# shield.net
KiCad netlist of a schematic drawn in EAGLE
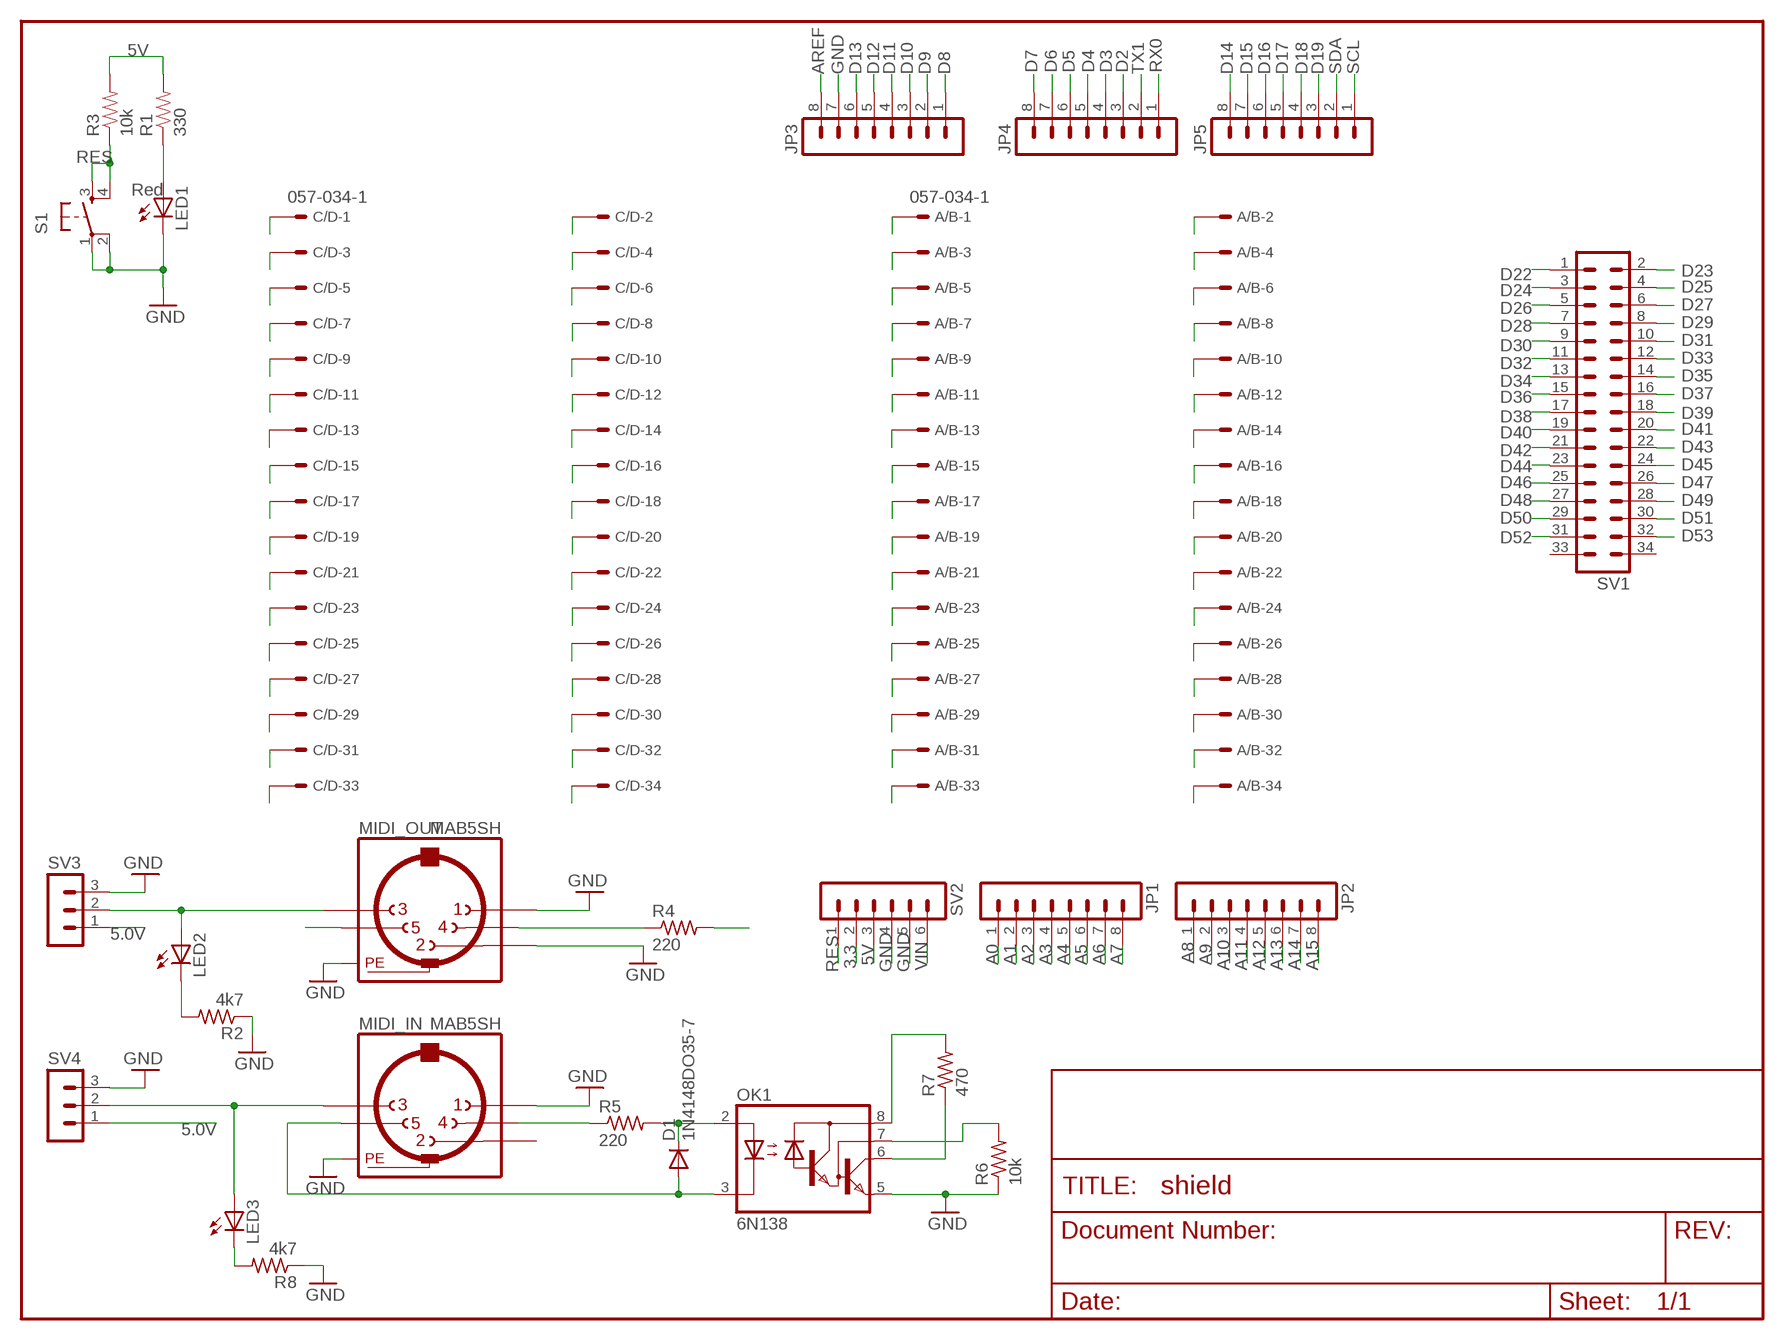
[diagram p0: schematic, sheet 1]

(export (version "E")
  (design (tool "Eeschema 10.0.6"))
  (components
    (comp (ref "A/B")
      (value "057-034-1")
      (footprint "eagle-import:057-034-1")
      (libsource (lib "eagle-import") (part "057-034-1"))
    )
    (comp (ref "C/D")
      (value "057-034-1")
      (footprint "eagle-import:057-034-1")
      (libsource (lib "eagle-import") (part "057-034-1"))
    )
    (comp (ref "D1")
      (value "1N4148DO35-7")
      (footprint "eagle-import:DO35-7")
      (libsource (lib "eagle-import") (part "1N4148DO35-7"))
    )
    (comp (ref "JP1")
      (value "MA08-1")
      (footprint "eagle-import:MA08-1")
      (libsource (lib "eagle-import") (part "MA08-1"))
    )
    (comp (ref "JP2")
      (value "MA08-1")
      (footprint "eagle-import:MA08-1")
      (libsource (lib "eagle-import") (part "MA08-1"))
    )
    (comp (ref "JP3")
      (value "MA08-1")
      (footprint "eagle-import:MA08-1")
      (libsource (lib "eagle-import") (part "MA08-1"))
    )
    (comp (ref "JP4")
      (value "MA08-1")
      (footprint "eagle-import:MA08-1")
      (libsource (lib "eagle-import") (part "MA08-1"))
    )
    (comp (ref "JP5")
      (value "MA08-1")
      (footprint "eagle-import:MA08-1")
      (libsource (lib "eagle-import") (part "MA08-1"))
    )
    (comp (ref "LED1")
      (value "Red")
      (footprint "eagle-import:LED5MM")
      (libsource (lib "eagle-import") (part "LED5MM"))
    )
    (comp (ref "LED2")
      (value "LEDLSU260")
      (footprint "eagle-import:LSU260")
      (libsource (lib "eagle-import") (part "LEDLSU260"))
    )
    (comp (ref "LED3")
      (value "LEDLSU260")
      (footprint "eagle-import:LSU260")
      (libsource (lib "eagle-import") (part "LEDLSU260"))
    )
    (comp (ref "MIDI_IN")
      (value "MAB5SH")
      (footprint "eagle-import:MAB5SH")
      (libsource (lib "eagle-import") (part "MAB5SH"))
    )
    (comp (ref "MIDI_OUT")
      (value "MAB5SH")
      (footprint "eagle-import:MAB5SH")
      (libsource (lib "eagle-import") (part "MAB5SH"))
    )
    (comp (ref "OK1")
      (value "6N138")
      (footprint "eagle-import:DIL08")
      (fields (field (name "MF") "VISHAY/TELEFUNKEN"))
      (libsource (lib "eagle-import") (part "6N138"))
    )
    (comp (ref "R1")
      (value "330")
      (footprint "eagle-import:AXIAL-0.3")
      (libsource (lib "eagle-import") (part "RESISTORPTH1"))
    )
    (comp (ref "R2")
      (value "4k7")
      (footprint "eagle-import:0204_7")
      (libsource (lib "eagle-import") (part "resistor_R-US_0204/7"))
    )
    (comp (ref "R3")
      (value "10k")
      (footprint "eagle-import:AXIAL-0.3")
      (libsource (lib "eagle-import") (part "RESISTORPTH1"))
    )
    (comp (ref "R4")
      (value "220")
      (footprint "eagle-import:0204_7")
      (libsource (lib "eagle-import") (part "R-US_0204/7"))
    )
    (comp (ref "R5")
      (value "220")
      (footprint "eagle-import:0204_7")
      (libsource (lib "eagle-import") (part "R-US_0204/7"))
    )
    (comp (ref "R6")
      (value "10k")
      (footprint "eagle-import:0204_7")
      (libsource (lib "eagle-import") (part "R-US_0204/7"))
    )
    (comp (ref "R7")
      (value "470")
      (footprint "eagle-import:0204_7")
      (libsource (lib "eagle-import") (part "R-US_0204/7"))
    )
    (comp (ref "R8")
      (value "4k7")
      (footprint "eagle-import:0204_7")
      (libsource (lib "eagle-import") (part "resistor_R-US_0204/7"))
    )
    (comp (ref "S1")
      (value "TAC_SWITCHPTH")
      (footprint "eagle-import:TACTILE-PTH")
      (libsource (lib "eagle-import") (part "TAC_SWITCHPTH"))
    )
    (comp (ref "SV1")
      (value "MA17-2")
      (footprint "eagle-import:MA17-2")
      (libsource (lib "eagle-import") (part "MA17-2"))
    )
    (comp (ref "SV2")
      (value "MA06-1")
      (footprint "eagle-import:MA06-1")
      (libsource (lib "eagle-import") (part "MA06-1"))
    )
    (comp (ref "SV3")
      (value "MA03-1")
      (footprint "eagle-import:MA03-1")
      (libsource (lib "eagle-import") (part "MA03-1"))
    )
    (comp (ref "SV4")
      (value "MA03-1")
      (footprint "eagle-import:MA03-1")
      (libsource (lib "eagle-import") (part "MA03-1"))
    )
  )
  (nets
    (net (code "1") (name "/3.3") (class "Default")
      (node (ref "SV2") (pin "2") (pinfunction "2_2") (pintype "passive"))
    )
    (net (code "2") (name "/5.0V") (class "Default")
      (node (ref "A/B") (pin "33") (pinfunction "S_33") (pintype "passive"))
      (node (ref "C/D") (pin "2") (pinfunction "S_2") (pintype "passive"))
      (node (ref "C/D") (pin "33") (pinfunction "S_33") (pintype "passive"))
      (node (ref "OK1") (pin "8") (pinfunction "VCC_8") (pintype "passive"))
      (node (ref "R1") (pin "P$2") (pinfunction "2_P$2") (pintype "passive"))
      (node (ref "R3") (pin "P$2") (pinfunction "2_P$2") (pintype "passive"))
      (node (ref "R4") (pin "2") (pinfunction "2_2") (pintype "passive"))
      (node (ref "R7") (pin "2") (pinfunction "2_2") (pintype "passive"))
      (node (ref "SV2") (pin "3") (pinfunction "3_3") (pintype "passive"))
      (node (ref "SV3") (pin "1") (pinfunction "1_1") (pintype "passive"))
      (node (ref "SV4") (pin "1") (pinfunction "1_1") (pintype "passive"))
    )
    (net (code "3") (name "/A0") (class "Default")
      (node (ref "JP1") (pin "1") (pinfunction "1_1") (pintype "passive"))
    )
    (net (code "4") (name "/A1") (class "Default")
      (node (ref "JP1") (pin "2") (pinfunction "2_2") (pintype "passive"))
    )
    (net (code "5") (name "/A2") (class "Default")
      (node (ref "JP1") (pin "3") (pinfunction "3_3") (pintype "passive"))
    )
    (net (code "6") (name "/A3") (class "Default")
      (node (ref "JP1") (pin "4") (pinfunction "4_4") (pintype "passive"))
    )
    (net (code "7") (name "/A4") (class "Default")
      (node (ref "C/D") (pin "9") (pinfunction "S_9") (pintype "passive"))
      (node (ref "JP1") (pin "5") (pinfunction "5_5") (pintype "passive"))
    )
    (net (code "8") (name "/A5") (class "Default")
      (node (ref "C/D") (pin "11") (pinfunction "S_11") (pintype "passive"))
      (node (ref "JP1") (pin "6") (pinfunction "6_6") (pintype "passive"))
    )
    (net (code "9") (name "/A6") (class "Default")
      (node (ref "C/D") (pin "13") (pinfunction "S_13") (pintype "passive"))
      (node (ref "JP1") (pin "7") (pinfunction "7_7") (pintype "passive"))
    )
    (net (code "10") (name "/A7") (class "Default")
      (node (ref "C/D") (pin "15") (pinfunction "S_15") (pintype "passive"))
      (node (ref "JP1") (pin "8") (pinfunction "8_8") (pintype "passive"))
    )
    (net (code "11") (name "/A8") (class "Default")
      (node (ref "C/D") (pin "17") (pinfunction "S_17") (pintype "passive"))
      (node (ref "JP2") (pin "1") (pinfunction "1_1") (pintype "passive"))
    )
    (net (code "12") (name "/A9") (class "Default")
      (node (ref "C/D") (pin "19") (pinfunction "S_19") (pintype "passive"))
      (node (ref "JP2") (pin "2") (pinfunction "2_2") (pintype "passive"))
    )
    (net (code "13") (name "/A10") (class "Default")
      (node (ref "C/D") (pin "21") (pinfunction "S_21") (pintype "passive"))
      (node (ref "JP2") (pin "3") (pinfunction "3_3") (pintype "passive"))
    )
    (net (code "14") (name "/A11") (class "Default")
      (node (ref "C/D") (pin "23") (pinfunction "S_23") (pintype "passive"))
      (node (ref "JP2") (pin "4") (pinfunction "4_4") (pintype "passive"))
    )
    (net (code "15") (name "/A12") (class "Default")
      (node (ref "C/D") (pin "25") (pinfunction "S_25") (pintype "passive"))
      (node (ref "JP2") (pin "5") (pinfunction "5_5") (pintype "passive"))
    )
    (net (code "16") (name "/A13") (class "Default")
      (node (ref "C/D") (pin "27") (pinfunction "S_27") (pintype "passive"))
      (node (ref "JP2") (pin "6") (pinfunction "6_6") (pintype "passive"))
    )
    (net (code "17") (name "/A14") (class "Default")
      (node (ref "C/D") (pin "29") (pinfunction "S_29") (pintype "passive"))
      (node (ref "JP2") (pin "7") (pinfunction "7_7") (pintype "passive"))
    )
    (net (code "18") (name "/A15") (class "Default")
      (node (ref "C/D") (pin "31") (pinfunction "S_31") (pintype "passive"))
      (node (ref "JP2") (pin "8") (pinfunction "8_8") (pintype "passive"))
    )
    (net (code "19") (name "/AREF") (class "Default")
      (node (ref "JP3") (pin "8") (pinfunction "8_8") (pintype "passive"))
    )
    (net (code "20") (name "/D2") (class "Default")
      (node (ref "A/B") (pin "26") (pinfunction "S_26") (pintype "passive"))
      (node (ref "JP4") (pin "3") (pinfunction "3_3") (pintype "passive"))
    )
    (net (code "21") (name "/D3") (class "Default")
      (node (ref "A/B") (pin "24") (pinfunction "S_24") (pintype "passive"))
      (node (ref "JP4") (pin "4") (pinfunction "4_4") (pintype "passive"))
    )
    (net (code "22") (name "/D4") (class "Default")
      (node (ref "A/B") (pin "22") (pinfunction "S_22") (pintype "passive"))
      (node (ref "JP4") (pin "5") (pinfunction "5_5") (pintype "passive"))
    )
    (net (code "23") (name "/D5") (class "Default")
      (node (ref "A/B") (pin "20") (pinfunction "S_20") (pintype "passive"))
      (node (ref "JP4") (pin "6") (pinfunction "6_6") (pintype "passive"))
    )
    (net (code "24") (name "/D6") (class "Default")
      (node (ref "A/B") (pin "18") (pinfunction "S_18") (pintype "passive"))
      (node (ref "JP4") (pin "7") (pinfunction "7_7") (pintype "passive"))
    )
    (net (code "25") (name "/D7") (class "Default")
      (node (ref "A/B") (pin "16") (pinfunction "S_16") (pintype "passive"))
      (node (ref "JP4") (pin "8") (pinfunction "8_8") (pintype "passive"))
    )
    (net (code "26") (name "/D8") (class "Default")
      (node (ref "A/B") (pin "14") (pinfunction "S_14") (pintype "passive"))
      (node (ref "JP3") (pin "1") (pinfunction "1_1") (pintype "passive"))
    )
    (net (code "27") (name "/D9") (class "Default")
      (node (ref "A/B") (pin "12") (pinfunction "S_12") (pintype "passive"))
      (node (ref "JP3") (pin "2") (pinfunction "2_2") (pintype "passive"))
    )
    (net (code "28") (name "/D10") (class "Default")
      (node (ref "A/B") (pin "10") (pinfunction "S_10") (pintype "passive"))
      (node (ref "JP3") (pin "3") (pinfunction "3_3") (pintype "passive"))
    )
    (net (code "29") (name "/D11") (class "Default")
      (node (ref "A/B") (pin "8") (pinfunction "S_8") (pintype "passive"))
      (node (ref "JP3") (pin "4") (pinfunction "4_4") (pintype "passive"))
    )
    (net (code "30") (name "/D12") (class "Default")
      (node (ref "A/B") (pin "6") (pinfunction "S_6") (pintype "passive"))
      (node (ref "JP3") (pin "5") (pinfunction "5_5") (pintype "passive"))
    )
    (net (code "31") (name "/D13") (class "Default")
      (node (ref "A/B") (pin "4") (pinfunction "S_4") (pintype "passive"))
      (node (ref "JP3") (pin "6") (pinfunction "6_6") (pintype "passive"))
    )
    (net (code "32") (name "/D14") (class "Default")
      (node (ref "JP5") (pin "8") (pinfunction "8_8") (pintype "passive"))
    )
    (net (code "33") (name "/D15") (class "Default")
      (node (ref "JP5") (pin "7") (pinfunction "7_7") (pintype "passive"))
    )
    (net (code "34") (name "/D16") (class "Default")
      (node (ref "JP5") (pin "6") (pinfunction "6_6") (pintype "passive"))
    )
    (net (code "35") (name "/D17") (class "Default")
      (node (ref "JP5") (pin "5") (pinfunction "5_5") (pintype "passive"))
    )
    (net (code "36") (name "/D18") (class "Default")
      (node (ref "JP5") (pin "4") (pinfunction "4_4") (pintype "passive"))
      (node (ref "MIDI_OUT") (pin "5") (pinfunction "5_5") (pintype "passive"))
    )
    (net (code "37") (name "/D19") (class "Default")
      (node (ref "JP5") (pin "3") (pinfunction "3_3") (pintype "passive"))
      (node (ref "OK1") (pin "6") (pinfunction "VO_6") (pintype "passive"))
      (node (ref "R7") (pin "1") (pinfunction "1_1") (pintype "passive"))
    )
    (net (code "38") (name "/D22") (class "Default")
      (node (ref "A/B") (pin "9") (pinfunction "S_9") (pintype "passive"))
      (node (ref "SV1") (pin "1") (pinfunction "1_1") (pintype "passive"))
    )
    (net (code "39") (name "/D23") (class "Default")
      (node (ref "A/B") (pin "11") (pinfunction "S_11") (pintype "passive"))
      (node (ref "SV1") (pin "2") (pinfunction "2_2") (pintype "passive"))
    )
    (net (code "40") (name "/D24") (class "Default")
      (node (ref "A/B") (pin "13") (pinfunction "S_13") (pintype "passive"))
      (node (ref "SV1") (pin "3") (pinfunction "3_3") (pintype "passive"))
    )
    (net (code "41") (name "/D25") (class "Default")
      (node (ref "A/B") (pin "15") (pinfunction "S_15") (pintype "passive"))
      (node (ref "SV1") (pin "4") (pinfunction "4_4") (pintype "passive"))
    )
    (net (code "42") (name "/D26") (class "Default")
      (node (ref "A/B") (pin "17") (pinfunction "S_17") (pintype "passive"))
      (node (ref "SV1") (pin "5") (pinfunction "5_5") (pintype "passive"))
    )
    (net (code "43") (name "/D27") (class "Default")
      (node (ref "A/B") (pin "19") (pinfunction "S_19") (pintype "passive"))
      (node (ref "SV1") (pin "6") (pinfunction "6_6") (pintype "passive"))
    )
    (net (code "44") (name "/D28") (class "Default")
      (node (ref "A/B") (pin "21") (pinfunction "S_21") (pintype "passive"))
      (node (ref "SV1") (pin "7") (pinfunction "7_7") (pintype "passive"))
    )
    (net (code "45") (name "/D29") (class "Default")
      (node (ref "A/B") (pin "31") (pinfunction "S_31") (pintype "passive"))
      (node (ref "SV1") (pin "8") (pinfunction "8_8") (pintype "passive"))
    )
    (net (code "46") (name "/D30") (class "Default")
      (node (ref "A/B") (pin "29") (pinfunction "S_29") (pintype "passive"))
      (node (ref "SV1") (pin "9") (pinfunction "9_9") (pintype "passive"))
    )
    (net (code "47") (name "/D31") (class "Default")
      (node (ref "A/B") (pin "27") (pinfunction "S_27") (pintype "passive"))
      (node (ref "SV1") (pin "10") (pinfunction "10_10") (pintype "passive"))
    )
    (net (code "48") (name "/D32") (class "Default")
      (node (ref "A/B") (pin "25") (pinfunction "S_25") (pintype "passive"))
      (node (ref "SV1") (pin "11") (pinfunction "11_11") (pintype "passive"))
    )
    (net (code "49") (name "/D33") (class "Default")
      (node (ref "A/B") (pin "23") (pinfunction "S_23") (pintype "passive"))
      (node (ref "SV1") (pin "12") (pinfunction "12_12") (pintype "passive"))
    )
    (net (code "50") (name "/D34") (class "Default")
      (node (ref "C/D") (pin "4") (pinfunction "S_4") (pintype "passive"))
      (node (ref "SV1") (pin "13") (pinfunction "13_13") (pintype "passive"))
    )
    (net (code "51") (name "/D35") (class "Default")
      (node (ref "C/D") (pin "6") (pinfunction "S_6") (pintype "passive"))
      (node (ref "SV1") (pin "14") (pinfunction "14_14") (pintype "passive"))
    )
    (net (code "52") (name "/D36") (class "Default")
      (node (ref "C/D") (pin "8") (pinfunction "S_8") (pintype "passive"))
      (node (ref "SV1") (pin "15") (pinfunction "15_15") (pintype "passive"))
    )
    (net (code "53") (name "/D37") (class "Default")
      (node (ref "C/D") (pin "10") (pinfunction "S_10") (pintype "passive"))
      (node (ref "SV1") (pin "16") (pinfunction "16_16") (pintype "passive"))
    )
    (net (code "54") (name "/D38") (class "Default")
      (node (ref "C/D") (pin "12") (pinfunction "S_12") (pintype "passive"))
      (node (ref "SV1") (pin "17") (pinfunction "17_17") (pintype "passive"))
    )
    (net (code "55") (name "/D39") (class "Default")
      (node (ref "C/D") (pin "14") (pinfunction "S_14") (pintype "passive"))
      (node (ref "SV1") (pin "18") (pinfunction "18_18") (pintype "passive"))
    )
    (net (code "56") (name "/D40") (class "Default")
      (node (ref "C/D") (pin "16") (pinfunction "S_16") (pintype "passive"))
      (node (ref "SV1") (pin "19") (pinfunction "19_19") (pintype "passive"))
    )
    (net (code "57") (name "/D41") (class "Default")
      (node (ref "C/D") (pin "18") (pinfunction "S_18") (pintype "passive"))
      (node (ref "SV1") (pin "20") (pinfunction "20_20") (pintype "passive"))
    )
    (net (code "58") (name "/D42") (class "Default")
      (node (ref "C/D") (pin "20") (pinfunction "S_20") (pintype "passive"))
      (node (ref "SV1") (pin "21") (pinfunction "21_21") (pintype "passive"))
    )
    (net (code "59") (name "/D43") (class "Default")
      (node (ref "C/D") (pin "22") (pinfunction "S_22") (pintype "passive"))
      (node (ref "SV1") (pin "22") (pinfunction "22_22") (pintype "passive"))
    )
    (net (code "60") (name "/D44") (class "Default")
      (node (ref "C/D") (pin "24") (pinfunction "S_24") (pintype "passive"))
      (node (ref "SV1") (pin "23") (pinfunction "23_23") (pintype "passive"))
    )
    (net (code "61") (name "/D45") (class "Default")
      (node (ref "C/D") (pin "26") (pinfunction "S_26") (pintype "passive"))
      (node (ref "SV1") (pin "24") (pinfunction "24_24") (pintype "passive"))
    )
    (net (code "62") (name "/D46") (class "Default")
      (node (ref "SV1") (pin "25") (pinfunction "25_25") (pintype "passive"))
    )
    (net (code "63") (name "/D47") (class "Default")
      (node (ref "SV1") (pin "26") (pinfunction "26_26") (pintype "passive"))
    )
    (net (code "64") (name "/D48") (class "Default")
      (node (ref "SV1") (pin "27") (pinfunction "27_27") (pintype "passive"))
    )
    (net (code "65") (name "/D49") (class "Default")
      (node (ref "SV1") (pin "28") (pinfunction "28_28") (pintype "passive"))
    )
    (net (code "66") (name "/D50") (class "Default")
      (node (ref "SV1") (pin "29") (pinfunction "29_29") (pintype "passive"))
    )
    (net (code "67") (name "/D51") (class "Default")
      (node (ref "SV1") (pin "30") (pinfunction "30_30") (pintype "passive"))
    )
    (net (code "68") (name "/D52") (class "Default")
      (node (ref "SV1") (pin "31") (pinfunction "31_31") (pintype "passive"))
    )
    (net (code "69") (name "/D53") (class "Default")
      (node (ref "SV1") (pin "32") (pinfunction "32_32") (pintype "passive"))
    )
    (net (code "70") (name "/RES") (class "Default")
      (node (ref "R3") (pin "P$1") (pinfunction "1_P$1") (pintype "passive"))
      (node (ref "S1") (pin "3") (pinfunction "3_3") (pintype "passive"))
      (node (ref "S1") (pin "4") (pinfunction "4_4") (pintype "passive"))
      (node (ref "SV2") (pin "1") (pinfunction "1_1") (pintype "passive"))
    )
    (net (code "71") (name "/RX0") (class "Default")
      (node (ref "JP4") (pin "1") (pinfunction "1_1") (pintype "passive"))
    )
    (net (code "72") (name "/SCL") (class "Default")
      (node (ref "JP5") (pin "1") (pinfunction "1_1") (pintype "passive"))
    )
    (net (code "73") (name "/SDA") (class "Default")
      (node (ref "JP5") (pin "2") (pinfunction "2_2") (pintype "passive"))
    )
    (net (code "74") (name "/TX1") (class "Default")
      (node (ref "JP4") (pin "2") (pinfunction "2_2") (pintype "passive"))
    )
    (net (code "75") (name "/VIN") (class "Default")
      (node (ref "SV2") (pin "6") (pinfunction "6_6") (pintype "passive"))
    )
    (net (code "76") (name "GND") (class "Default")
      (node (ref "A/B") (pin "34") (pinfunction "S_34") (pintype "passive"))
      (node (ref "C/D") (pin "34") (pinfunction "S_34") (pintype "passive"))
      (node (ref "JP3") (pin "7") (pinfunction "7_7") (pintype "passive"))
      (node (ref "LED1") (pin "K") (pinfunction "C_K") (pintype "passive"))
      (node (ref "MIDI_IN") (pin "1") (pinfunction "1_1") (pintype "passive"))
      (node (ref "MIDI_IN") (pin "PE") (pinfunction "PE_PE") (pintype "power_in"))
      (node (ref "MIDI_IN") (pin "PE@") (pinfunction "PE_PE@") (pintype "power_in"))
      (node (ref "MIDI_OUT") (pin "1") (pinfunction "1_1") (pintype "passive"))
      (node (ref "MIDI_OUT") (pin "2") (pinfunction "2_2") (pintype "passive"))
      (node (ref "MIDI_OUT") (pin "PE") (pinfunction "PE_PE") (pintype "power_in"))
      (node (ref "MIDI_OUT") (pin "PE@") (pinfunction "PE_PE@") (pintype "power_in"))
      (node (ref "OK1") (pin "5") (pinfunction "GND_5") (pintype "passive"))
      (node (ref "R2") (pin "1") (pinfunction "1_1") (pintype "passive"))
      (node (ref "R6") (pin "1") (pinfunction "1_1") (pintype "passive"))
      (node (ref "R8") (pin "1") (pinfunction "1_1") (pintype "passive"))
      (node (ref "S1") (pin "1") (pinfunction "1_1") (pintype "passive"))
      (node (ref "S1") (pin "2") (pinfunction "2_2") (pintype "passive"))
      (node (ref "SV2") (pin "4") (pinfunction "4_4") (pintype "passive"))
      (node (ref "SV2") (pin "5") (pinfunction "5_5") (pintype "passive"))
      (node (ref "SV3") (pin "3") (pinfunction "3_3") (pintype "passive"))
      (node (ref "SV4") (pin "3") (pinfunction "3_3") (pintype "passive"))
    )
    (net (code "77") (name "Net-(LED2-C)") (class "Default")
      (node (ref "LED2") (pin "K") (pinfunction "C_K") (pintype "passive"))
      (node (ref "R2") (pin "2") (pinfunction "2_2") (pintype "passive"))
    )
    (net (code "78") (name "Net-(LED2-PadA)") (class "Default")
      (node (ref "LED2") (pin "A") (pinfunction "A_A") (pintype "passive"))
      (node (ref "MIDI_OUT") (pin "3") (pinfunction "3_3") (pintype "passive"))
      (node (ref "SV3") (pin "2") (pinfunction "2_2") (pintype "passive"))
    )
    (net (code "79") (name "Net-(LED3-C)") (class "Default")
      (node (ref "LED3") (pin "K") (pinfunction "C_K") (pintype "passive"))
      (node (ref "R8") (pin "2") (pinfunction "2_2") (pintype "passive"))
    )
    (net (code "80") (name "Net-(LED3-PadA)") (class "Default")
      (node (ref "LED3") (pin "A") (pinfunction "A_A") (pintype "passive"))
      (node (ref "MIDI_IN") (pin "3") (pinfunction "3_3") (pintype "passive"))
      (node (ref "SV4") (pin "2") (pinfunction "2_2") (pintype "passive"))
    )
    (net (code "81") (name "Net-(MIDI_IN-Pad4)") (class "Default")
      (node (ref "MIDI_IN") (pin "4") (pinfunction "4_4") (pintype "passive"))
      (node (ref "R5") (pin "1") (pinfunction "1_1") (pintype "passive"))
    )
    (net (code "82") (name "Net-(MIDI_OUT-Pad4)") (class "Default")
      (node (ref "MIDI_OUT") (pin "4") (pinfunction "4_4") (pintype "passive"))
      (node (ref "R4") (pin "1") (pinfunction "1_1") (pintype "passive"))
    )
    (net (code "83") (name "Net-(OK1-A)") (class "Default")
      (node (ref "D1") (pin "C") (pinfunction "C_C") (pintype "passive"))
      (node (ref "OK1") (pin "2") (pinfunction "A_2") (pintype "passive"))
      (node (ref "R5") (pin "2") (pinfunction "2_2") (pintype "passive"))
    )
    (net (code "84") (name "Net-(OK1-C)") (class "Default")
      (node (ref "D1") (pin "A") (pinfunction "A_A") (pintype "passive"))
      (node (ref "MIDI_IN") (pin "5") (pinfunction "5_5") (pintype "passive"))
      (node (ref "OK1") (pin "3") (pinfunction "C_3") (pintype "passive"))
    )
    (net (code "85") (name "Net-(OK1-VB)") (class "Default")
      (node (ref "OK1") (pin "7") (pinfunction "VB_7") (pintype "passive"))
      (node (ref "R6") (pin "2") (pinfunction "2_2") (pintype "passive"))
    )
    (net (code "86") (name "Net-(R1-1)") (class "Default")
      (node (ref "LED1") (pin "A") (pinfunction "A_A") (pintype "passive"))
      (node (ref "R1") (pin "P$1") (pinfunction "1_P$1") (pintype "passive"))
    )
    (net (code "87") (name "unconnected-(A/BA-S-Pad1)") (class "Default")
      (node (ref "A/B") (pin "1") (pinfunction "S_1") (pintype "passive"))
    )
    (net (code "88") (name "unconnected-(A/BAD-S-Pad5)") (class "Default")
      (node (ref "A/B") (pin "5") (pinfunction "S_5") (pintype "passive"))
    )
    (net (code "89") (name "unconnected-(A/BAF-S-Pad7)") (class "Default")
      (node (ref "A/B") (pin "7") (pinfunction "S_7") (pintype "passive"))
    )
    (net (code "90") (name "unconnected-(A/BL-S-Pad2)") (class "Default")
      (node (ref "A/B") (pin "2") (pinfunction "S_2") (pintype "passive"))
    )
    (net (code "91") (name "unconnected-(A/BU-S-Pad28)") (class "Default")
      (node (ref "A/B") (pin "28") (pinfunction "S_28") (pintype "passive"))
    )
    (net (code "92") (name "unconnected-(A/BW-S-Pad3)") (class "Default")
      (node (ref "A/B") (pin "3") (pinfunction "S_3") (pintype "passive"))
    )
    (net (code "93") (name "unconnected-(A/BX-S-Pad30)") (class "Default")
      (node (ref "A/B") (pin "30") (pinfunction "S_30") (pintype "passive"))
    )
    (net (code "94") (name "unconnected-(A/BZ-S-Pad32)") (class "Default")
      (node (ref "A/B") (pin "32") (pinfunction "S_32") (pintype "passive"))
    )
    (net (code "95") (name "unconnected-(C/DA-S-Pad1)") (class "Default")
      (node (ref "C/D") (pin "1") (pinfunction "S_1") (pintype "passive"))
    )
    (net (code "96") (name "unconnected-(C/DAD-S-Pad5)") (class "Default")
      (node (ref "C/D") (pin "5") (pinfunction "S_5") (pintype "passive"))
    )
    (net (code "97") (name "unconnected-(C/DAF-S-Pad7)") (class "Default")
      (node (ref "C/D") (pin "7") (pinfunction "S_7") (pintype "passive"))
    )
    (net (code "98") (name "unconnected-(C/DU-S-Pad28)") (class "Default")
      (node (ref "C/D") (pin "28") (pinfunction "S_28") (pintype "passive"))
    )
    (net (code "99") (name "unconnected-(C/DW-S-Pad3)") (class "Default")
      (node (ref "C/D") (pin "3") (pinfunction "S_3") (pintype "passive"))
    )
    (net (code "100") (name "unconnected-(C/DX-S-Pad30)") (class "Default")
      (node (ref "C/D") (pin "30") (pinfunction "S_30") (pintype "passive"))
    )
    (net (code "101") (name "unconnected-(C/DZ-S-Pad32)") (class "Default")
      (node (ref "C/D") (pin "32") (pinfunction "S_32") (pintype "passive"))
    )
    (net (code "102") (name "unconnected-(MIDI_IN-Pad2)") (class "Default")
      (node (ref "MIDI_IN") (pin "2") (pinfunction "2_2") (pintype "passive"))
    )
    (net (code "103") (name "unconnected-(SV1-Pad33)") (class "Default")
      (node (ref "SV1") (pin "33") (pinfunction "33_33") (pintype "passive"))
    )
    (net (code "104") (name "unconnected-(SV1-Pad34)") (class "Default")
      (node (ref "SV1") (pin "34") (pinfunction "34_34") (pintype "passive"))
    )
  )
)
